# SCH_Genie-V1_2024-07-31.net
KiCad netlist of a schematic drawn in EasyEDA
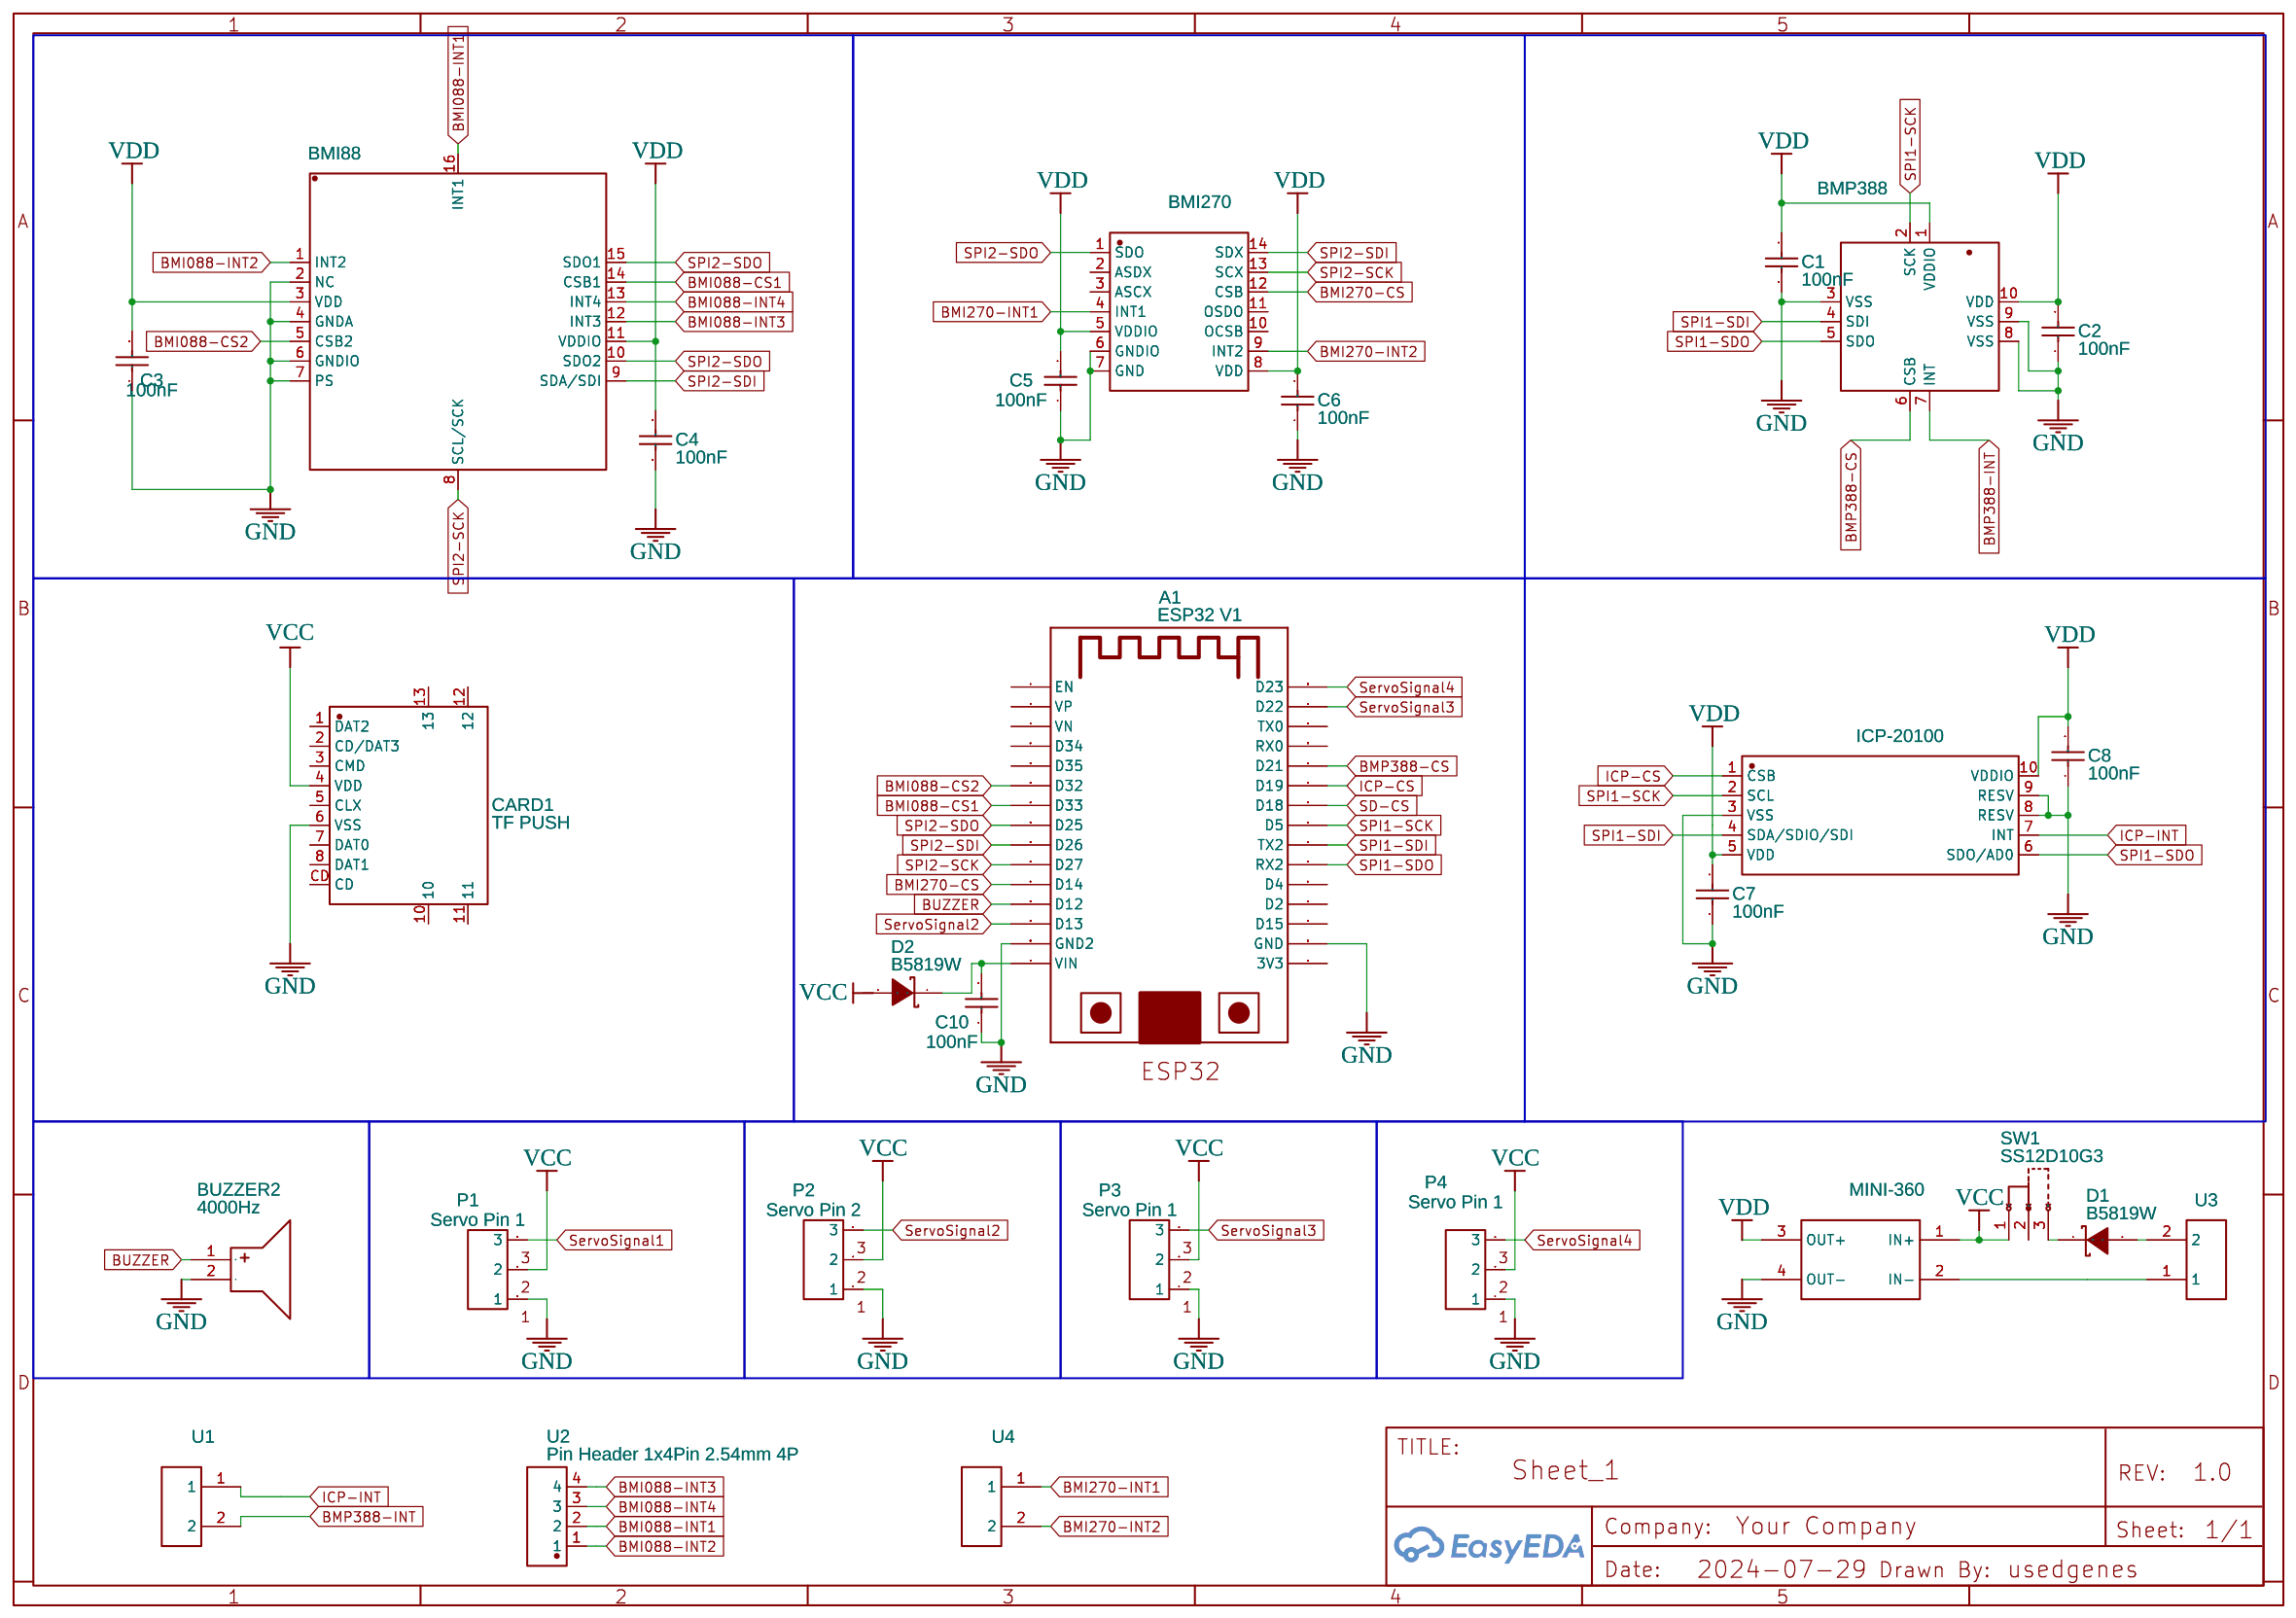
[diagram p0: schematic sheet]

(export (version "E")
  (design (tool "Eeschema 10.0.6"))
  (components
    (comp (ref "A1") (value "ESP32 V1") (libsource (lib "") (part "ESP32-DEVKIT-V1-30PIN")))
    (comp (ref "BMI88")
      (value "BMI088")
      (fields (field (name "Manufacturer") "Bosch(博世)"))
      (libsource (lib "") (part "BMI088"))
    )
    (comp (ref "BMI270")
      (value "BMI270")
      (fields (field (name "Manufacturer") "Bosch(博世)"))
      (libsource (lib "") (part "BMI270"))
    )
    (comp (ref "BMP388")
      (value "BMP388")
      (fields (field (name "Manufacturer") "Bosch(博世)"))
      (libsource (lib "") (part "BMP388"))
    )
    (comp (ref "BUZZER2")
      (value "4000Hz")
      (fields
        (field (name "Manufacturer Part") "SKY-1475-0540-45P7.6")
        (field (name "Manufacturer") "S&S(海旭)")
      )
      (libsource (lib "") (part "SKY-1475-0540-45P7.6"))
    )
    (comp (ref "C1")
      (value "100nF")
      (fields
        (field (name "Manufacturer Part") "CL05B104KO5NNNC")
        (field (name "Manufacturer") "SAMSUNG(三星)")
      )
      (libsource (lib "") (part "CL05B104KO5NNNC"))
    )
    (comp (ref "C2")
      (value "100nF")
      (fields
        (field (name "Manufacturer Part") "CL05B104KO5NNNC")
        (field (name "Manufacturer") "SAMSUNG(三星)")
      )
      (libsource (lib "") (part "CL05B104KO5NNNC"))
    )
    (comp (ref "C3")
      (value "100nF")
      (fields
        (field (name "Manufacturer Part") "CL05B104KO5NNNC")
        (field (name "Manufacturer") "SAMSUNG(三星)")
      )
      (libsource (lib "") (part "CL05B104KO5NNNC"))
    )
    (comp (ref "C4")
      (value "100nF")
      (fields
        (field (name "Manufacturer Part") "CL05B104KO5NNNC")
        (field (name "Manufacturer") "SAMSUNG(三星)")
      )
      (libsource (lib "") (part "CL05B104KO5NNNC"))
    )
    (comp (ref "C5")
      (value "100nF")
      (fields
        (field (name "Manufacturer Part") "CL05B104KO5NNNC")
        (field (name "Manufacturer") "SAMSUNG(三星)")
      )
      (libsource (lib "") (part "CL05B104KO5NNNC"))
    )
    (comp (ref "C6")
      (value "100nF")
      (fields
        (field (name "Manufacturer Part") "CL05B104KO5NNNC")
        (field (name "Manufacturer") "SAMSUNG(三星)")
      )
      (libsource (lib "") (part "CL05B104KO5NNNC"))
    )
    (comp (ref "C7")
      (value "100nF")
      (fields
        (field (name "Manufacturer Part") "CL05B104KO5NNNC")
        (field (name "Manufacturer") "SAMSUNG(三星)")
      )
      (libsource (lib "") (part "CL05B104KO5NNNC"))
    )
    (comp (ref "C8")
      (value "100nF")
      (fields
        (field (name "Manufacturer Part") "CL05B104KO5NNNC")
        (field (name "Manufacturer") "SAMSUNG(三星)")
      )
      (libsource (lib "") (part "CL05B104KO5NNNC"))
    )
    (comp (ref "C10")
      (value "100nF")
      (fields
        (field (name "Manufacturer Part") "CL05B104KO5NNNC")
        (field (name "Manufacturer") "SAMSUNG(三星)")
      )
      (libsource (lib "") (part "CL05B104KO5NNNC"))
    )
    (comp (ref "CARD1")
      (value "TF PUSH")
      (fields (field (name "Manufacturer") "SHOU HAN(首韩)"))
      (libsource (lib "") (part "TF PUSH"))
    )
    (comp (ref "D1")
      (value "B5819W")
      (fields (field (name "Manufacturer") "MDD(辰达半导体)"))
      (libsource (lib "") (part "B5819W"))
    )
    (comp (ref "D2")
      (value "B5819W")
      (fields (field (name "Manufacturer") "MDD(辰达半导体)"))
      (libsource (lib "") (part "B5819W_1"))
    )
    (comp (ref "ICP-20100")
      (value "ICP-20100")
      (fields (field (name "Manufacturer") "TDK"))
      (libsource (lib "") (part "ICP-20100"))
    )
    (comp (ref "MINI-360") (value "MINI-360") (libsource (lib "") (part "MINI-360")))
    (comp (ref "P1")
      (value "Servo Pin 1")
      (fields
        (field (name "Manufacturer Part") "Female headerHDR1X8-2.54")
        (field (name "Manufacturer") "BOOMELE")
      )
      (libsource (lib "") (part "HEADER PAD 3X RMM COPY"))
    )
    (comp (ref "P2")
      (value "Servo Pin 2")
      (fields
        (field (name "Manufacturer Part") "Female headerHDR1X8-2.54")
        (field (name "Manufacturer") "BOOMELE")
      )
      (libsource (lib "") (part "HEADER PAD 3X RMM COPY"))
    )
    (comp (ref "P3")
      (value "Servo Pin 1")
      (fields
        (field (name "Manufacturer Part") "Female headerHDR1X8-2.54")
        (field (name "Manufacturer") "BOOMELE")
      )
      (libsource (lib "") (part "HEADER PAD 3X RMM COPY"))
    )
    (comp (ref "P4")
      (value "Servo Pin 1")
      (fields
        (field (name "Manufacturer Part") "Female headerHDR1X8-2.54")
        (field (name "Manufacturer") "BOOMELE")
      )
      (libsource (lib "") (part "HEADER PAD 3X RMM COPY"))
    )
    (comp (ref "SW1")
      (value "SS12D10G3")
      (fields (field (name "Manufacturer") "SHOU HAN(首韩)"))
      (libsource (lib "") (part "SS12D10G3"))
    )
    (comp (ref "U1") (value "Power Pins") (libsource (lib "") (part "1X2")))
    (comp (ref "U2")
      (value "Pin Header 1x4Pin 2.54mm 4P")
      (libsource (lib "") (part "Pin Header 1x4Pin 2.54mm 4P"))
    )
    (comp (ref "U3") (value "Power Pins") (libsource (lib "") (part "1X2_1")))
    (comp (ref "U4") (value "Power Pins") (libsource (lib "") (part "1X2")))
  )
  (nets
    (net (code "1") (name "BMI088-CS1") (class "Default")
      (node (ref "A1") (pin "D33") (pinfunction "D33_D33") (pintype "unspecified"))
      (node (ref "BMI88") (pin "14") (pinfunction "CSB1_14") (pintype "unspecified"))
    )
    (net (code "2") (name "BMI088-CS2") (class "Default")
      (node (ref "A1") (pin "D32") (pinfunction "D32_D32") (pintype "unspecified"))
      (node (ref "BMI88") (pin "5") (pinfunction "CSB2_5") (pintype "unspecified"))
    )
    (net (code "3") (name "BMI088-INT1") (class "Default")
      (node (ref "BMI88") (pin "16") (pinfunction "INT1_16") (pintype "unspecified"))
      (node (ref "U2") (pin "2") (pinfunction "2_2") (pintype "unspecified"))
    )
    (net (code "4") (name "BMI088-INT2") (class "Default")
      (node (ref "BMI88") (pin "1") (pinfunction "INT2_1") (pintype "unspecified"))
      (node (ref "U2") (pin "1") (pinfunction "1_1") (pintype "unspecified"))
    )
    (net (code "5") (name "BMI088-INT3") (class "Default")
      (node (ref "BMI88") (pin "12") (pinfunction "INT3_12") (pintype "unspecified"))
      (node (ref "U2") (pin "4") (pinfunction "4_4") (pintype "unspecified"))
    )
    (net (code "6") (name "BMI088-INT4") (class "Default")
      (node (ref "BMI88") (pin "13") (pinfunction "INT4_13") (pintype "unspecified"))
      (node (ref "U2") (pin "3") (pinfunction "3_3") (pintype "unspecified"))
    )
    (net (code "7") (name "BMI270-CS") (class "Default")
      (node (ref "A1") (pin "D14") (pinfunction "D14_D14") (pintype "unspecified"))
      (node (ref "BMI270") (pin "12") (pinfunction "CSB_12") (pintype "unspecified"))
    )
    (net (code "8") (name "BMI270-INT1") (class "Default")
      (node (ref "BMI270") (pin "4") (pinfunction "INT1_4") (pintype "unspecified"))
      (node (ref "U4") (pin "1") (pinfunction "1_1") (pintype "unspecified"))
    )
    (net (code "9") (name "BMI270-INT2") (class "Default")
      (node (ref "BMI270") (pin "9") (pinfunction "INT2_9") (pintype "unspecified"))
      (node (ref "U4") (pin "2") (pinfunction "2_2") (pintype "unspecified"))
    )
    (net (code "10") (name "BMP388-CS") (class "Default")
      (node (ref "A1") (pin "D21") (pinfunction "D21_D21") (pintype "unspecified"))
      (node (ref "BMP388") (pin "6") (pinfunction "CSB_6") (pintype "unspecified"))
    )
    (net (code "11") (name "BMP388-INT") (class "Default")
      (node (ref "BMP388") (pin "7") (pinfunction "INT_7") (pintype "unspecified"))
      (node (ref "U1") (pin "2") (pinfunction "2_2") (pintype "unspecified"))
    )
    (net (code "12") (name "BUZZER") (class "Default")
      (node (ref "A1") (pin "D12") (pinfunction "D12_D12") (pintype "unspecified"))
      (node (ref "BUZZER2") (pin "1") (pinfunction "+_1") (pintype "unspecified"))
    )
    (net (code "13") (name "GND") (class "Default")
      (node (ref "A1") (pin "GND") (pinfunction "GND_GND") (pintype "unspecified"))
      (node (ref "A1") (pin "GND2") (pinfunction "GND2_GND2") (pintype "unspecified"))
      (node (ref "BMI270") (pin "6") (pinfunction "GNDIO_6") (pintype "unspecified"))
      (node (ref "BMI270") (pin "7") (pinfunction "GND_7") (pintype "unspecified"))
      (node (ref "BMI88") (pin "2") (pinfunction "NC_2") (pintype "unspecified"))
      (node (ref "BMI88") (pin "4") (pinfunction "GNDA_4") (pintype "unspecified"))
      (node (ref "BMI88") (pin "6") (pinfunction "GNDIO_6") (pintype "unspecified"))
      (node (ref "BMI88") (pin "7") (pinfunction "PS_7") (pintype "unspecified"))
      (node (ref "BMP388") (pin "3") (pinfunction "VSS_3") (pintype "unspecified"))
      (node (ref "BMP388") (pin "8") (pinfunction "VSS_8") (pintype "unspecified"))
      (node (ref "BMP388") (pin "9") (pinfunction "VSS_9") (pintype "unspecified"))
      (node (ref "BUZZER2") (pin "2") (pinfunction "-_2") (pintype "unspecified"))
      (node (ref "C1") (pin "1") (pinfunction "1_1") (pintype "input"))
      (node (ref "C10") (pin "1") (pinfunction "1_1") (pintype "input"))
      (node (ref "C2") (pin "1") (pinfunction "1_1") (pintype "input"))
      (node (ref "C3") (pin "1") (pinfunction "1_1") (pintype "input"))
      (node (ref "C4") (pin "1") (pinfunction "1_1") (pintype "input"))
      (node (ref "C5") (pin "1") (pinfunction "1_1") (pintype "input"))
      (node (ref "C6") (pin "1") (pinfunction "1_1") (pintype "input"))
      (node (ref "C7") (pin "1") (pinfunction "1_1") (pintype "input"))
      (node (ref "C8") (pin "1") (pinfunction "1_1") (pintype "input"))
      (node (ref "CARD1") (pin "6") (pinfunction "VSS_6") (pintype "unspecified"))
      (node (ref "ICP-20100") (pin "3") (pinfunction "VSS_3") (pintype "unspecified"))
      (node (ref "ICP-20100") (pin "8") (pinfunction "RESV_8") (pintype "unspecified"))
      (node (ref "ICP-20100") (pin "9") (pinfunction "RESV_9") (pintype "unspecified"))
      (node (ref "MINI-360") (pin "4") (pinfunction "OUT-_4") (pintype "unspecified"))
      (node (ref "P1") (pin "1") (pinfunction "1_1") (pintype "unspecified"))
      (node (ref "P2") (pin "1") (pinfunction "1_1") (pintype "unspecified"))
      (node (ref "P3") (pin "1") (pinfunction "1_1") (pintype "unspecified"))
      (node (ref "P4") (pin "1") (pinfunction "1_1") (pintype "unspecified"))
    )
    (net (code "14") (name "ICP-CS") (class "Default")
      (node (ref "A1") (pin "D19") (pinfunction "D19_D19") (pintype "unspecified"))
      (node (ref "ICP-20100") (pin "1") (pinfunction "CSB_1") (pintype "unspecified"))
    )
    (net (code "15") (name "ICP-INT") (class "Default")
      (node (ref "ICP-20100") (pin "7") (pinfunction "INT_7") (pintype "unspecified"))
      (node (ref "U1") (pin "1") (pinfunction "1_1") (pintype "unspecified"))
    )
    (net (code "16") (name "Net-(D1-A)") (class "Default")
      (node (ref "D1") (pin "2") (pinfunction "A_2") (pintype "unspecified"))
      (node (ref "U3") (pin "2") (pinfunction "2_2") (pintype "unspecified"))
    )
    (net (code "17") (name "Net-(D1-K)") (class "Default")
      (node (ref "D1") (pin "1") (pinfunction "K_1") (pintype "unspecified"))
      (node (ref "SW1") (pin "3") (pinfunction "3_3") (pintype "unspecified"))
    )
    (net (code "18") (name "Net-(D2-K)") (class "Default")
      (node (ref "A1") (pin "VIN") (pinfunction "VIN_VIN") (pintype "unspecified"))
      (node (ref "C10") (pin "2") (pinfunction "2_2") (pintype "input"))
      (node (ref "D2") (pin "1") (pinfunction "K_1") (pintype "unspecified"))
    )
    (net (code "19") (name "Net-(MINI-360-IN-)") (class "Default")
      (node (ref "MINI-360") (pin "2") (pinfunction "IN-_2") (pintype "unspecified"))
      (node (ref "U3") (pin "1") (pinfunction "1_1") (pintype "unspecified"))
    )
    (net (code "20") (name "SD-CS") (class "Default")
      (node (ref "A1") (pin "D18") (pinfunction "D18_D18") (pintype "unspecified"))
    )
    (net (code "21") (name "SPI1-SCK") (class "Default")
      (node (ref "A1") (pin "D5") (pinfunction "D5_D5") (pintype "unspecified"))
      (node (ref "BMP388") (pin "2") (pinfunction "SCK_2") (pintype "unspecified"))
      (node (ref "ICP-20100") (pin "2") (pinfunction "SCL_2") (pintype "unspecified"))
    )
    (net (code "22") (name "SPI1-SDI") (class "Default")
      (node (ref "A1") (pin "TX2") (pinfunction "TX2_TX2") (pintype "unspecified"))
      (node (ref "BMP388") (pin "4") (pinfunction "SDI_4") (pintype "unspecified"))
      (node (ref "ICP-20100") (pin "4") (pinfunction "SDA/SDIO/SDI_4") (pintype "unspecified"))
    )
    (net (code "23") (name "SPI1-SDO") (class "Default")
      (node (ref "A1") (pin "RX2") (pinfunction "RX2_RX2") (pintype "unspecified"))
      (node (ref "BMP388") (pin "5") (pinfunction "SDO_5") (pintype "unspecified"))
      (node (ref "ICP-20100") (pin "6") (pinfunction "SDO/AD0_6") (pintype "unspecified"))
    )
    (net (code "24") (name "SPI2-SCK") (class "Default")
      (node (ref "A1") (pin "D27") (pinfunction "D27_D27") (pintype "unspecified"))
      (node (ref "BMI270") (pin "13") (pinfunction "SCX_13") (pintype "unspecified"))
      (node (ref "BMI88") (pin "8") (pinfunction "SCL/SCK_8") (pintype "unspecified"))
    )
    (net (code "25") (name "SPI2-SDI") (class "Default")
      (node (ref "A1") (pin "D26") (pinfunction "D26_D26") (pintype "unspecified"))
      (node (ref "BMI270") (pin "14") (pinfunction "SDX_14") (pintype "unspecified"))
      (node (ref "BMI88") (pin "9") (pinfunction "SDA/SDI_9") (pintype "unspecified"))
    )
    (net (code "26") (name "SPI2-SDO") (class "Default")
      (node (ref "A1") (pin "D25") (pinfunction "D25_D25") (pintype "unspecified"))
      (node (ref "BMI270") (pin "1") (pinfunction "SDO_1") (pintype "unspecified"))
      (node (ref "BMI88") (pin "10") (pinfunction "SDO2_10") (pintype "unspecified"))
      (node (ref "BMI88") (pin "15") (pinfunction "SDO1_15") (pintype "unspecified"))
    )
    (net (code "27") (name "ServoSignal1") (class "Default")
      (node (ref "P1") (pin "3") (pinfunction "3_3") (pintype "unspecified"))
    )
    (net (code "28") (name "ServoSignal2") (class "Default")
      (node (ref "A1") (pin "D13") (pinfunction "D13_D13") (pintype "unspecified"))
      (node (ref "P2") (pin "3") (pinfunction "3_3") (pintype "unspecified"))
    )
    (net (code "29") (name "ServoSignal3") (class "Default")
      (node (ref "A1") (pin "D22") (pinfunction "D22_D22") (pintype "unspecified"))
      (node (ref "P3") (pin "3") (pinfunction "3_3") (pintype "unspecified"))
    )
    (net (code "30") (name "ServoSignal4") (class "Default")
      (node (ref "A1") (pin "D23") (pinfunction "D23_D23") (pintype "unspecified"))
      (node (ref "P4") (pin "3") (pinfunction "3_3") (pintype "unspecified"))
    )
    (net (code "31") (name "VCC") (class "Default")
      (node (ref "CARD1") (pin "4") (pinfunction "VDD_4") (pintype "unspecified"))
      (node (ref "D2") (pin "2") (pinfunction "A_2") (pintype "unspecified"))
      (node (ref "MINI-360") (pin "1") (pinfunction "IN+_1") (pintype "unspecified"))
      (node (ref "P1") (pin "2") (pinfunction "2_2") (pintype "unspecified"))
      (node (ref "P2") (pin "2") (pinfunction "2_2") (pintype "unspecified"))
      (node (ref "P3") (pin "2") (pinfunction "2_2") (pintype "unspecified"))
      (node (ref "P4") (pin "2") (pinfunction "2_2") (pintype "unspecified"))
      (node (ref "SW1") (pin "1") (pinfunction "1_1") (pintype "unspecified"))
    )
    (net (code "32") (name "VDD") (class "Default")
      (node (ref "BMI270") (pin "5") (pinfunction "VDDIO_5") (pintype "unspecified"))
      (node (ref "BMI270") (pin "8") (pinfunction "VDD_8") (pintype "unspecified"))
      (node (ref "BMI88") (pin "11") (pinfunction "VDDIO_11") (pintype "unspecified"))
      (node (ref "BMI88") (pin "3") (pinfunction "VDD_3") (pintype "unspecified"))
      (node (ref "BMP388") (pin "1") (pinfunction "VDDIO_1") (pintype "unspecified"))
      (node (ref "BMP388") (pin "10") (pinfunction "VDD_10") (pintype "unspecified"))
      (node (ref "C1") (pin "2") (pinfunction "2_2") (pintype "input"))
      (node (ref "C2") (pin "2") (pinfunction "2_2") (pintype "input"))
      (node (ref "C3") (pin "2") (pinfunction "2_2") (pintype "input"))
      (node (ref "C4") (pin "2") (pinfunction "2_2") (pintype "input"))
      (node (ref "C5") (pin "2") (pinfunction "2_2") (pintype "input"))
      (node (ref "C6") (pin "2") (pinfunction "2_2") (pintype "input"))
      (node (ref "C7") (pin "2") (pinfunction "2_2") (pintype "input"))
      (node (ref "C8") (pin "2") (pinfunction "2_2") (pintype "input"))
      (node (ref "ICP-20100") (pin "10") (pinfunction "VDDIO_10") (pintype "unspecified"))
      (node (ref "ICP-20100") (pin "5") (pinfunction "VDD_5") (pintype "unspecified"))
      (node (ref "MINI-360") (pin "3") (pinfunction "OUT+_3") (pintype "unspecified"))
    )
    (net (code "33") (name "unconnected-(A1-Pad3V3)") (class "Default")
      (node (ref "A1") (pin "3V3") (pinfunction "3V3_3V3") (pintype "unspecified"))
    )
    (net (code "34") (name "unconnected-(A1-PadD2)") (class "Default")
      (node (ref "A1") (pin "D2") (pinfunction "D2_D2") (pintype "unspecified"))
    )
    (net (code "35") (name "unconnected-(A1-PadD4)") (class "Default")
      (node (ref "A1") (pin "D4") (pinfunction "D4_D4") (pintype "unspecified"))
    )
    (net (code "36") (name "unconnected-(A1-PadD15)") (class "Default")
      (node (ref "A1") (pin "D15") (pinfunction "D15_D15") (pintype "unspecified"))
    )
    (net (code "37") (name "unconnected-(A1-PadD34)") (class "Default")
      (node (ref "A1") (pin "D34") (pinfunction "D34_D34") (pintype "unspecified"))
    )
    (net (code "38") (name "unconnected-(A1-PadD35)") (class "Default")
      (node (ref "A1") (pin "D35") (pinfunction "D35_D35") (pintype "unspecified"))
    )
    (net (code "39") (name "unconnected-(A1-PadEN)") (class "Default")
      (node (ref "A1") (pin "EN") (pinfunction "EN_EN") (pintype "unspecified"))
    )
    (net (code "40") (name "unconnected-(A1-PadRX0)") (class "Default")
      (node (ref "A1") (pin "RX0") (pinfunction "RX0_RX0") (pintype "unspecified"))
    )
    (net (code "41") (name "unconnected-(A1-PadTX0)") (class "Default")
      (node (ref "A1") (pin "TX0") (pinfunction "TX0_TX0") (pintype "unspecified"))
    )
    (net (code "42") (name "unconnected-(A1-PadVN)") (class "Default")
      (node (ref "A1") (pin "VN") (pinfunction "VN_VN") (pintype "unspecified"))
    )
    (net (code "43") (name "unconnected-(A1-PadVP)") (class "Default")
      (node (ref "A1") (pin "VP") (pinfunction "VP_VP") (pintype "unspecified"))
    )
    (net (code "44") (name "unconnected-(BMI270-ASCX-Pad3)") (class "Default")
      (node (ref "BMI270") (pin "3") (pinfunction "ASCX_3") (pintype "unspecified"))
    )
    (net (code "45") (name "unconnected-(BMI270-ASDX-Pad2)") (class "Default")
      (node (ref "BMI270") (pin "2") (pinfunction "ASDX_2") (pintype "unspecified"))
    )
    (net (code "46") (name "unconnected-(BMI270-OCSB-Pad10)") (class "Default")
      (node (ref "BMI270") (pin "10") (pinfunction "OCSB_10") (pintype "unspecified"))
    )
    (net (code "47") (name "unconnected-(BMI270-OSDO-Pad11)") (class "Default")
      (node (ref "BMI270") (pin "11") (pinfunction "OSDO_11") (pintype "unspecified"))
    )
    (net (code "48") (name "unconnected-(CARD1-CD{slash}DAT3-Pad2)") (class "Default")
      (node (ref "CARD1") (pin "2") (pinfunction "CD/DAT3_2") (pintype "unspecified"))
    )
    (net (code "49") (name "unconnected-(CARD1-CLX-Pad5)") (class "Default")
      (node (ref "CARD1") (pin "5") (pinfunction "CLX_5") (pintype "unspecified"))
    )
    (net (code "50") (name "unconnected-(CARD1-CMD-Pad3)") (class "Default")
      (node (ref "CARD1") (pin "3") (pinfunction "CMD_3") (pintype "unspecified"))
    )
    (net (code "51") (name "unconnected-(CARD1-DAT0-Pad7)") (class "Default")
      (node (ref "CARD1") (pin "7") (pinfunction "DAT0_7") (pintype "unspecified"))
    )
    (net (code "52") (name "unconnected-(CARD1-DAT1-Pad8)") (class "Default")
      (node (ref "CARD1") (pin "8") (pinfunction "DAT1_8") (pintype "unspecified"))
    )
    (net (code "53") (name "unconnected-(CARD1-DAT2-Pad1)") (class "Default")
      (node (ref "CARD1") (pin "1") (pinfunction "DAT2_1") (pintype "unspecified"))
    )
    (net (code "54") (name "unconnected-(CARD1-Pad10)") (class "Default")
      (node (ref "CARD1") (pin "10") (pinfunction "10_10") (pintype "unspecified"))
    )
    (net (code "55") (name "unconnected-(CARD1-Pad11)") (class "Default")
      (node (ref "CARD1") (pin "11") (pinfunction "11_11") (pintype "unspecified"))
    )
    (net (code "56") (name "unconnected-(CARD1-Pad12)") (class "Default")
      (node (ref "CARD1") (pin "12") (pinfunction "12_12") (pintype "unspecified"))
    )
    (net (code "57") (name "unconnected-(CARD1-Pad13)") (class "Default")
      (node (ref "CARD1") (pin "13") (pinfunction "13_13") (pintype "unspecified"))
    )
    (net (code "58") (name "unconnected-(CARD1-PadCD)") (class "Default")
      (node (ref "CARD1") (pin "CD") (pinfunction "CD_CD") (pintype "unspecified"))
    )
    (net (code "59") (name "unconnected-(SW1-Pad2)") (class "Default")
      (node (ref "SW1") (pin "2") (pinfunction "2_2") (pintype "unspecified"))
    )
  )
)
